# target_mcu.net
KiCad netlist of a schematic drawn in Altium Designer
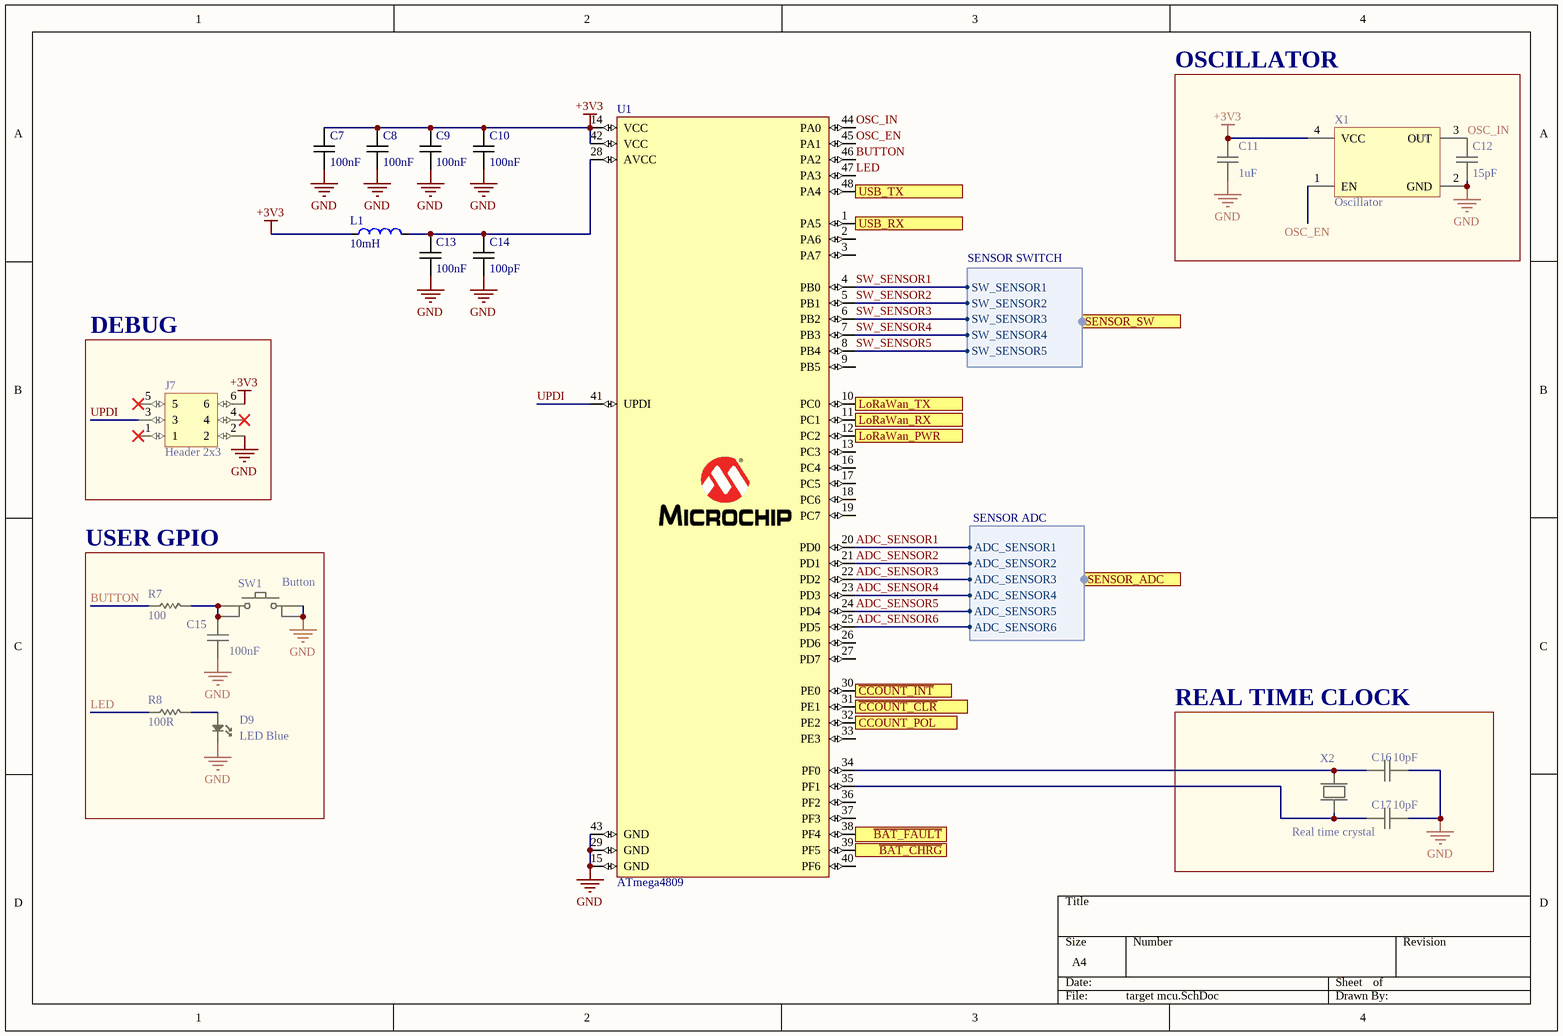
[diagram p0: target mcu.SchDoc]

(export (version "E")
  (design (tool "Eeschema 10.0.6"))
  (components
    (comp (ref "C7")
      (value "100nF")
      (footprint "C0402")
      (fields (field (name "Comment") "Capacitor 0402"))
      (libsource (lib "altium-import") (part "root_1_Capacitor 0402_"))
    )
    (comp (ref "C8")
      (value "100nF")
      (footprint "C0402")
      (fields (field (name "Comment") "Capacitor 0402"))
      (libsource (lib "altium-import") (part "root_1_Capacitor 0402_"))
    )
    (comp (ref "C9")
      (value "100nF")
      (footprint "C0402")
      (fields (field (name "Comment") "Capacitor 0402"))
      (libsource (lib "altium-import") (part "root_1_Capacitor 0402_"))
    )
    (comp (ref "C10")
      (value "100nF")
      (footprint "C0402")
      (fields (field (name "Comment") "Capacitor 0402"))
      (libsource (lib "altium-import") (part "root_1_Capacitor 0402_"))
    )
    (comp (ref "C11")
      (value "1uF")
      (footprint "C0603")
      (fields (field (name "Comment") "Capacitor 0603"))
      (libsource (lib "altium-import") (part "root_1_Capacitor 0603_"))
    )
    (comp (ref "C12")
      (value "15pF")
      (footprint "C0603")
      (fields (field (name "Comment") "Capacitor 0603"))
      (libsource (lib "altium-import") (part "root_1_Capacitor 0603_"))
    )
    (comp (ref "C13")
      (value "100nF")
      (footprint "C0402")
      (fields (field (name "Comment") "Capacitor 0402"))
      (libsource (lib "altium-import") (part "root_1_Capacitor 0402_"))
    )
    (comp (ref "C14")
      (value "100pF")
      (footprint "C0402")
      (fields (field (name "Comment") "Capacitor 0402"))
      (libsource (lib "altium-import") (part "root_1_Capacitor 0402_"))
    )
    (comp (ref "C15")
      (value "100nF")
      (footprint "C0603")
      (fields (field (name "Comment") "Capacitor 0603"))
      (libsource (lib "altium-import") (part "root_1_Capacitor 0603_"))
    )
    (comp (ref "C16")
      (value "10pF")
      (footprint "C0603")
      (fields (field (name "Comment") "Capacitor 0603"))
      (libsource (lib "Passive components") (part "Capacitor 0603"))
    )
    (comp (ref "C17")
      (value "10pF")
      (footprint "C0603")
      (fields (field (name "Comment") "Capacitor 0603"))
      (libsource (lib "Passive components") (part "Capacitor 0603"))
    )
    (comp (ref "D9")
      (value "LED Blue")
      (footprint "L0603 BLUE")
      (libsource (lib "altium-import") (part "root_3_LED 0603 Blue_"))
    )
    (comp (ref "J7")
      (value "Header 2x3")
      (footprint "Header 2x3 Male")
      (libsource (lib "Connectors") (part "Header  2x3 Male"))
    )
    (comp (ref "L1")
      (value "10mH")
      (footprint "Inductor 0603")
      (fields (field (name "Comment") "Inductor 0603"))
      (libsource (lib "altium-import") (part "root_0_Inductor 0603_"))
    )
    (comp (ref "R7")
      (value "100")
      (footprint "R0603")
      (fields (field (name "Comment") "Resistor 0603"))
      (libsource (lib "altium-import") (part "root_0_Resistor 0603_"))
    )
    (comp (ref "R8")
      (value "100R")
      (footprint "R0603")
      (fields (field (name "Comment") "Resistor 0603"))
      (libsource (lib "altium-import") (part "root_0_Resistor 0603_"))
    )
    (comp (ref "SW1")
      (value "Button")
      (footprint "Button SMD")
      (libsource (lib "altium-import") (part "root_0_Button SMD_"))
    )
    (comp (ref "U1")
      (value "ATmega4809")
      (footprint "ATmega4809")
      (libsource (lib "altium-import") (part "root_0_ATmega4809_"))
    )
    (comp (ref "X1")
      (value "Oscillator")
      (footprint "Crystal SMD 3.2x2.5")
      (libsource (lib "altium-import") (part "root_0_Oscillator 3.2x2.5mm_"))
    )
    (comp (ref "X2")
      (value "Real time crystal")
      (footprint "Realtime crystal SMD 4.2x1.45mm")
      (libsource (lib "Crystals") (part "Realtime crystal SMD 5.2x1.45mm"))
    )
  )
  (nets
    (net (code "4") (name "+3V3") (class "Default")
      (node (ref "C10") (pin "2") (pinfunction "2_2") (pintype "passive"))
      (node (ref "C11") (pin "2") (pinfunction "2_2") (pintype "passive"))
      (node (ref "C7") (pin "2") (pinfunction "2_2") (pintype "passive"))
      (node (ref "C8") (pin "2") (pinfunction "2_2") (pintype "passive"))
      (node (ref "C9") (pin "2") (pinfunction "2_2") (pintype "passive"))
      (node (ref "J7") (pin "6") (pinfunction "6_6") (pintype "bidirectional"))
      (node (ref "L1") (pin "1") (pinfunction "1_1") (pintype "passive"))
      (node (ref "U1") (pin "14") (pinfunction "VCC_14") (pintype "bidirectional"))
      (node (ref "U1") (pin "42") (pinfunction "VCC_42") (pintype "bidirectional"))
      (node (ref "X1") (pin "4") (pinfunction "VCC_4") (pintype "passive"))
    )
    (net (code "5") (name "/ADC_SENSOR1") (class "Default")
      (node (ref "U1") (pin "20") (pinfunction "PD0_20") (pintype "bidirectional"))
    )
    (net (code "6") (name "/ADC_SENSOR2") (class "Default")
      (node (ref "U1") (pin "21") (pinfunction "PD1_21") (pintype "bidirectional"))
    )
    (net (code "7") (name "/ADC_SENSOR3") (class "Default")
      (node (ref "U1") (pin "22") (pinfunction "PD2_22") (pintype "bidirectional"))
    )
    (net (code "8") (name "/ADC_SENSOR4") (class "Default")
      (node (ref "U1") (pin "23") (pinfunction "PD3_23") (pintype "bidirectional"))
    )
    (net (code "9") (name "/ADC_SENSOR5") (class "Default")
      (node (ref "U1") (pin "24") (pinfunction "PD4_24") (pintype "bidirectional"))
    )
    (net (code "10") (name "/ADC_SENSOR6") (class "Default")
      (node (ref "U1") (pin "25") (pinfunction "PD5_25") (pintype "bidirectional"))
    )
    (net (code "11") (name "/BUTTON") (class "Default")
      (node (ref "R7") (pin "1") (pinfunction "1_1") (pintype "passive"))
      (node (ref "U1") (pin "46") (pinfunction "PA2_46") (pintype "bidirectional"))
    )
    (net (code "12") (name "/CCOUNT_POL") (class "Default")
      (node (ref "U1") (pin "32") (pinfunction "PE2_32") (pintype "bidirectional"))
    )
    (net (code "13") (name "/LED") (class "Default")
      (node (ref "R8") (pin "1") (pinfunction "1_1") (pintype "passive"))
      (node (ref "U1") (pin "47") (pinfunction "PA3_47") (pintype "bidirectional"))
    )
    (net (code "14") (name "/LoRaWan_PWR") (class "Default")
      (node (ref "U1") (pin "12") (pinfunction "PC2_12") (pintype "bidirectional"))
    )
    (net (code "15") (name "/LoRaWan_RX") (class "Default")
      (node (ref "U1") (pin "11") (pinfunction "PC1_11") (pintype "bidirectional"))
    )
    (net (code "16") (name "/LoRaWan_TX") (class "Default")
      (node (ref "U1") (pin "10") (pinfunction "PC0_10") (pintype "bidirectional"))
    )
    (net (code "17") (name "/OSC_EN") (class "Default")
      (node (ref "U1") (pin "45") (pinfunction "PA1_45") (pintype "bidirectional"))
      (node (ref "X1") (pin "1") (pinfunction "EN_1") (pintype "passive"))
    )
    (net (code "18") (name "/OSC_IN") (class "Default")
      (node (ref "C12") (pin "2") (pinfunction "2_2") (pintype "passive"))
      (node (ref "U1") (pin "44") (pinfunction "PA0_44") (pintype "bidirectional"))
      (node (ref "X1") (pin "3") (pinfunction "OUT_3") (pintype "passive"))
    )
    (net (code "19") (name "/SW_SENSOR1") (class "Default")
      (node (ref "U1") (pin "4") (pinfunction "PB0_4") (pintype "bidirectional"))
    )
    (net (code "20") (name "/SW_SENSOR2") (class "Default")
      (node (ref "U1") (pin "5") (pinfunction "PB1_5") (pintype "bidirectional"))
    )
    (net (code "21") (name "/SW_SENSOR3") (class "Default")
      (node (ref "U1") (pin "6") (pinfunction "PB2_6") (pintype "bidirectional"))
    )
    (net (code "22") (name "/SW_SENSOR4") (class "Default")
      (node (ref "U1") (pin "7") (pinfunction "PB3_7") (pintype "bidirectional"))
    )
    (net (code "23") (name "/SW_SENSOR5") (class "Default")
      (node (ref "U1") (pin "8") (pinfunction "PB4_8") (pintype "bidirectional"))
    )
    (net (code "24") (name "/UPDI") (class "Default")
      (node (ref "J7") (pin "3") (pinfunction "3_3") (pintype "bidirectional"))
      (node (ref "U1") (pin "41") (pinfunction "UPDI_41") (pintype "bidirectional"))
    )
    (net (code "25") (name "/USB_RX") (class "Default")
      (node (ref "U1") (pin "1") (pinfunction "PA5_1") (pintype "bidirectional"))
    )
    (net (code "26") (name "/USB_TX") (class "Default")
      (node (ref "U1") (pin "48") (pinfunction "PA4_48") (pintype "bidirectional"))
    )
    (net (code "29") (name "/~{BAT_CHRG}") (class "Default")
      (node (ref "U1") (pin "39") (pinfunction "PF5_39") (pintype "bidirectional"))
    )
    (net (code "30") (name "/~{BAT_FAULT}") (class "Default")
      (node (ref "U1") (pin "38") (pinfunction "PF4_38") (pintype "bidirectional"))
    )
    (net (code "31") (name "/~{CCOUNT_CLR}") (class "Default")
      (node (ref "U1") (pin "31") (pinfunction "PE1_31") (pintype "bidirectional"))
    )
    (net (code "32") (name "/~{CCOUNT_INT}") (class "Default")
      (node (ref "U1") (pin "30") (pinfunction "PE0_30") (pintype "bidirectional"))
    )
    (net (code "33") (name "GND") (class "Default")
      (node (ref "C10") (pin "1") (pinfunction "1_1") (pintype "passive"))
      (node (ref "C11") (pin "1") (pinfunction "1_1") (pintype "passive"))
      (node (ref "C12") (pin "1") (pinfunction "1_1") (pintype "passive"))
      (node (ref "C13") (pin "1") (pinfunction "1_1") (pintype "passive"))
      (node (ref "C14") (pin "1") (pinfunction "1_1") (pintype "passive"))
      (node (ref "C15") (pin "1") (pinfunction "1_1") (pintype "passive"))
      (node (ref "C16") (pin "2") (pinfunction "2_2") (pintype "passive"))
      (node (ref "C17") (pin "2") (pinfunction "2_2") (pintype "passive"))
      (node (ref "C7") (pin "1") (pinfunction "1_1") (pintype "passive"))
      (node (ref "C8") (pin "1") (pinfunction "1_1") (pintype "passive"))
      (node (ref "C9") (pin "1") (pinfunction "1_1") (pintype "passive"))
      (node (ref "D9") (pin "2") (pinfunction "2_2") (pintype "passive"))
      (node (ref "J7") (pin "2") (pinfunction "2_2") (pintype "bidirectional"))
      (node (ref "SW1") (pin "3") (pinfunction "3_3") (pintype "passive"))
      (node (ref "SW1") (pin "4") (pinfunction "4_4") (pintype "passive"))
      (node (ref "U1") (pin "15") (pinfunction "GND_15") (pintype "bidirectional"))
      (node (ref "U1") (pin "29") (pinfunction "GND_29") (pintype "bidirectional"))
      (node (ref "U1") (pin "43") (pinfunction "GND_43") (pintype "bidirectional"))
      (node (ref "X1") (pin "2") (pinfunction "GND_2") (pintype "passive"))
    )
    (net (code "34") (name "Net-(C15-Pad2)") (class "Default")
      (node (ref "C15") (pin "2") (pinfunction "2_2") (pintype "passive"))
      (node (ref "R7") (pin "2") (pinfunction "2_2") (pintype "passive"))
      (node (ref "SW1") (pin "1") (pinfunction "1_1") (pintype "passive"))
      (node (ref "SW1") (pin "2") (pinfunction "2_2") (pintype "passive"))
    )
    (net (code "35") (name "Net-(D9-Pad1)") (class "Default")
      (node (ref "D9") (pin "1") (pinfunction "1_1") (pintype "passive"))
      (node (ref "R8") (pin "2") (pinfunction "2_2") (pintype "passive"))
    )
    (net (code "36") (name "Net-(U1-AVCC)") (class "Default")
      (node (ref "C13") (pin "2") (pinfunction "2_2") (pintype "passive"))
      (node (ref "C14") (pin "2") (pinfunction "2_2") (pintype "passive"))
      (node (ref "L1") (pin "2") (pinfunction "2_2") (pintype "passive"))
      (node (ref "U1") (pin "28") (pinfunction "AVCC_28") (pintype "bidirectional"))
    )
    (net (code "37") (name "Net-(U1-PF0)") (class "Default")
      (node (ref "C16") (pin "1") (pinfunction "1_1") (pintype "passive"))
      (node (ref "U1") (pin "34") (pinfunction "PF0_34") (pintype "bidirectional"))
      (node (ref "X2") (pin "2") (pinfunction "1_2") (pintype "passive"))
    )
    (net (code "38") (name "Net-(U1-PF1)") (class "Default")
      (node (ref "C17") (pin "1") (pinfunction "1_1") (pintype "passive"))
      (node (ref "U1") (pin "35") (pinfunction "PF1_35") (pintype "bidirectional"))
      (node (ref "X2") (pin "1") (pinfunction "3_1") (pintype "passive"))
    )
    (net (code "39") (name "unconnected-(J7-Pad1)") (class "Default")
      (node (ref "J7") (pin "1") (pinfunction "1_1") (pintype "bidirectional+no_connect"))
    )
    (net (code "40") (name "unconnected-(J7-Pad4)") (class "Default")
      (node (ref "J7") (pin "4") (pinfunction "4_4") (pintype "bidirectional+no_connect"))
    )
    (net (code "41") (name "unconnected-(J7-Pad5)") (class "Default")
      (node (ref "J7") (pin "5") (pinfunction "5_5") (pintype "bidirectional+no_connect"))
    )
    (net (code "42") (name "unconnected-(U1-PA6-Pad2)") (class "Default")
      (node (ref "U1") (pin "2") (pinfunction "PA6_2") (pintype "bidirectional"))
    )
    (net (code "43") (name "unconnected-(U1-PA7-Pad3)") (class "Default")
      (node (ref "U1") (pin "3") (pinfunction "PA7_3") (pintype "bidirectional"))
    )
    (net (code "44") (name "unconnected-(U1-PB5-Pad9)") (class "Default")
      (node (ref "U1") (pin "9") (pinfunction "PB5_9") (pintype "bidirectional"))
    )
    (net (code "45") (name "unconnected-(U1-PC3-Pad13)") (class "Default")
      (node (ref "U1") (pin "13") (pinfunction "PC3_13") (pintype "bidirectional"))
    )
    (net (code "46") (name "unconnected-(U1-PC4-Pad16)") (class "Default")
      (node (ref "U1") (pin "16") (pinfunction "PC4_16") (pintype "bidirectional"))
    )
    (net (code "47") (name "unconnected-(U1-PC5-Pad17)") (class "Default")
      (node (ref "U1") (pin "17") (pinfunction "PC5_17") (pintype "bidirectional"))
    )
    (net (code "48") (name "unconnected-(U1-PC6-Pad18)") (class "Default")
      (node (ref "U1") (pin "18") (pinfunction "PC6_18") (pintype "bidirectional"))
    )
    (net (code "49") (name "unconnected-(U1-PC7-Pad19)") (class "Default")
      (node (ref "U1") (pin "19") (pinfunction "PC7_19") (pintype "bidirectional"))
    )
    (net (code "50") (name "unconnected-(U1-PD6-Pad26)") (class "Default")
      (node (ref "U1") (pin "26") (pinfunction "PD6_26") (pintype "bidirectional"))
    )
    (net (code "51") (name "unconnected-(U1-PD7-Pad27)") (class "Default")
      (node (ref "U1") (pin "27") (pinfunction "PD7_27") (pintype "bidirectional"))
    )
    (net (code "52") (name "unconnected-(U1-PE3-Pad33)") (class "Default")
      (node (ref "U1") (pin "33") (pinfunction "PE3_33") (pintype "bidirectional"))
    )
    (net (code "53") (name "unconnected-(U1-PF2-Pad36)") (class "Default")
      (node (ref "U1") (pin "36") (pinfunction "PF2_36") (pintype "bidirectional"))
    )
    (net (code "54") (name "unconnected-(U1-PF3-Pad37)") (class "Default")
      (node (ref "U1") (pin "37") (pinfunction "PF3_37") (pintype "bidirectional"))
    )
    (net (code "55") (name "unconnected-(U1-PF6-Pad40)") (class "Default")
      (node (ref "U1") (pin "40") (pinfunction "PF6_40") (pintype "bidirectional"))
    )
  )
)
